# design.net
KiCad netlist of a schematic drawn in Altium Designer
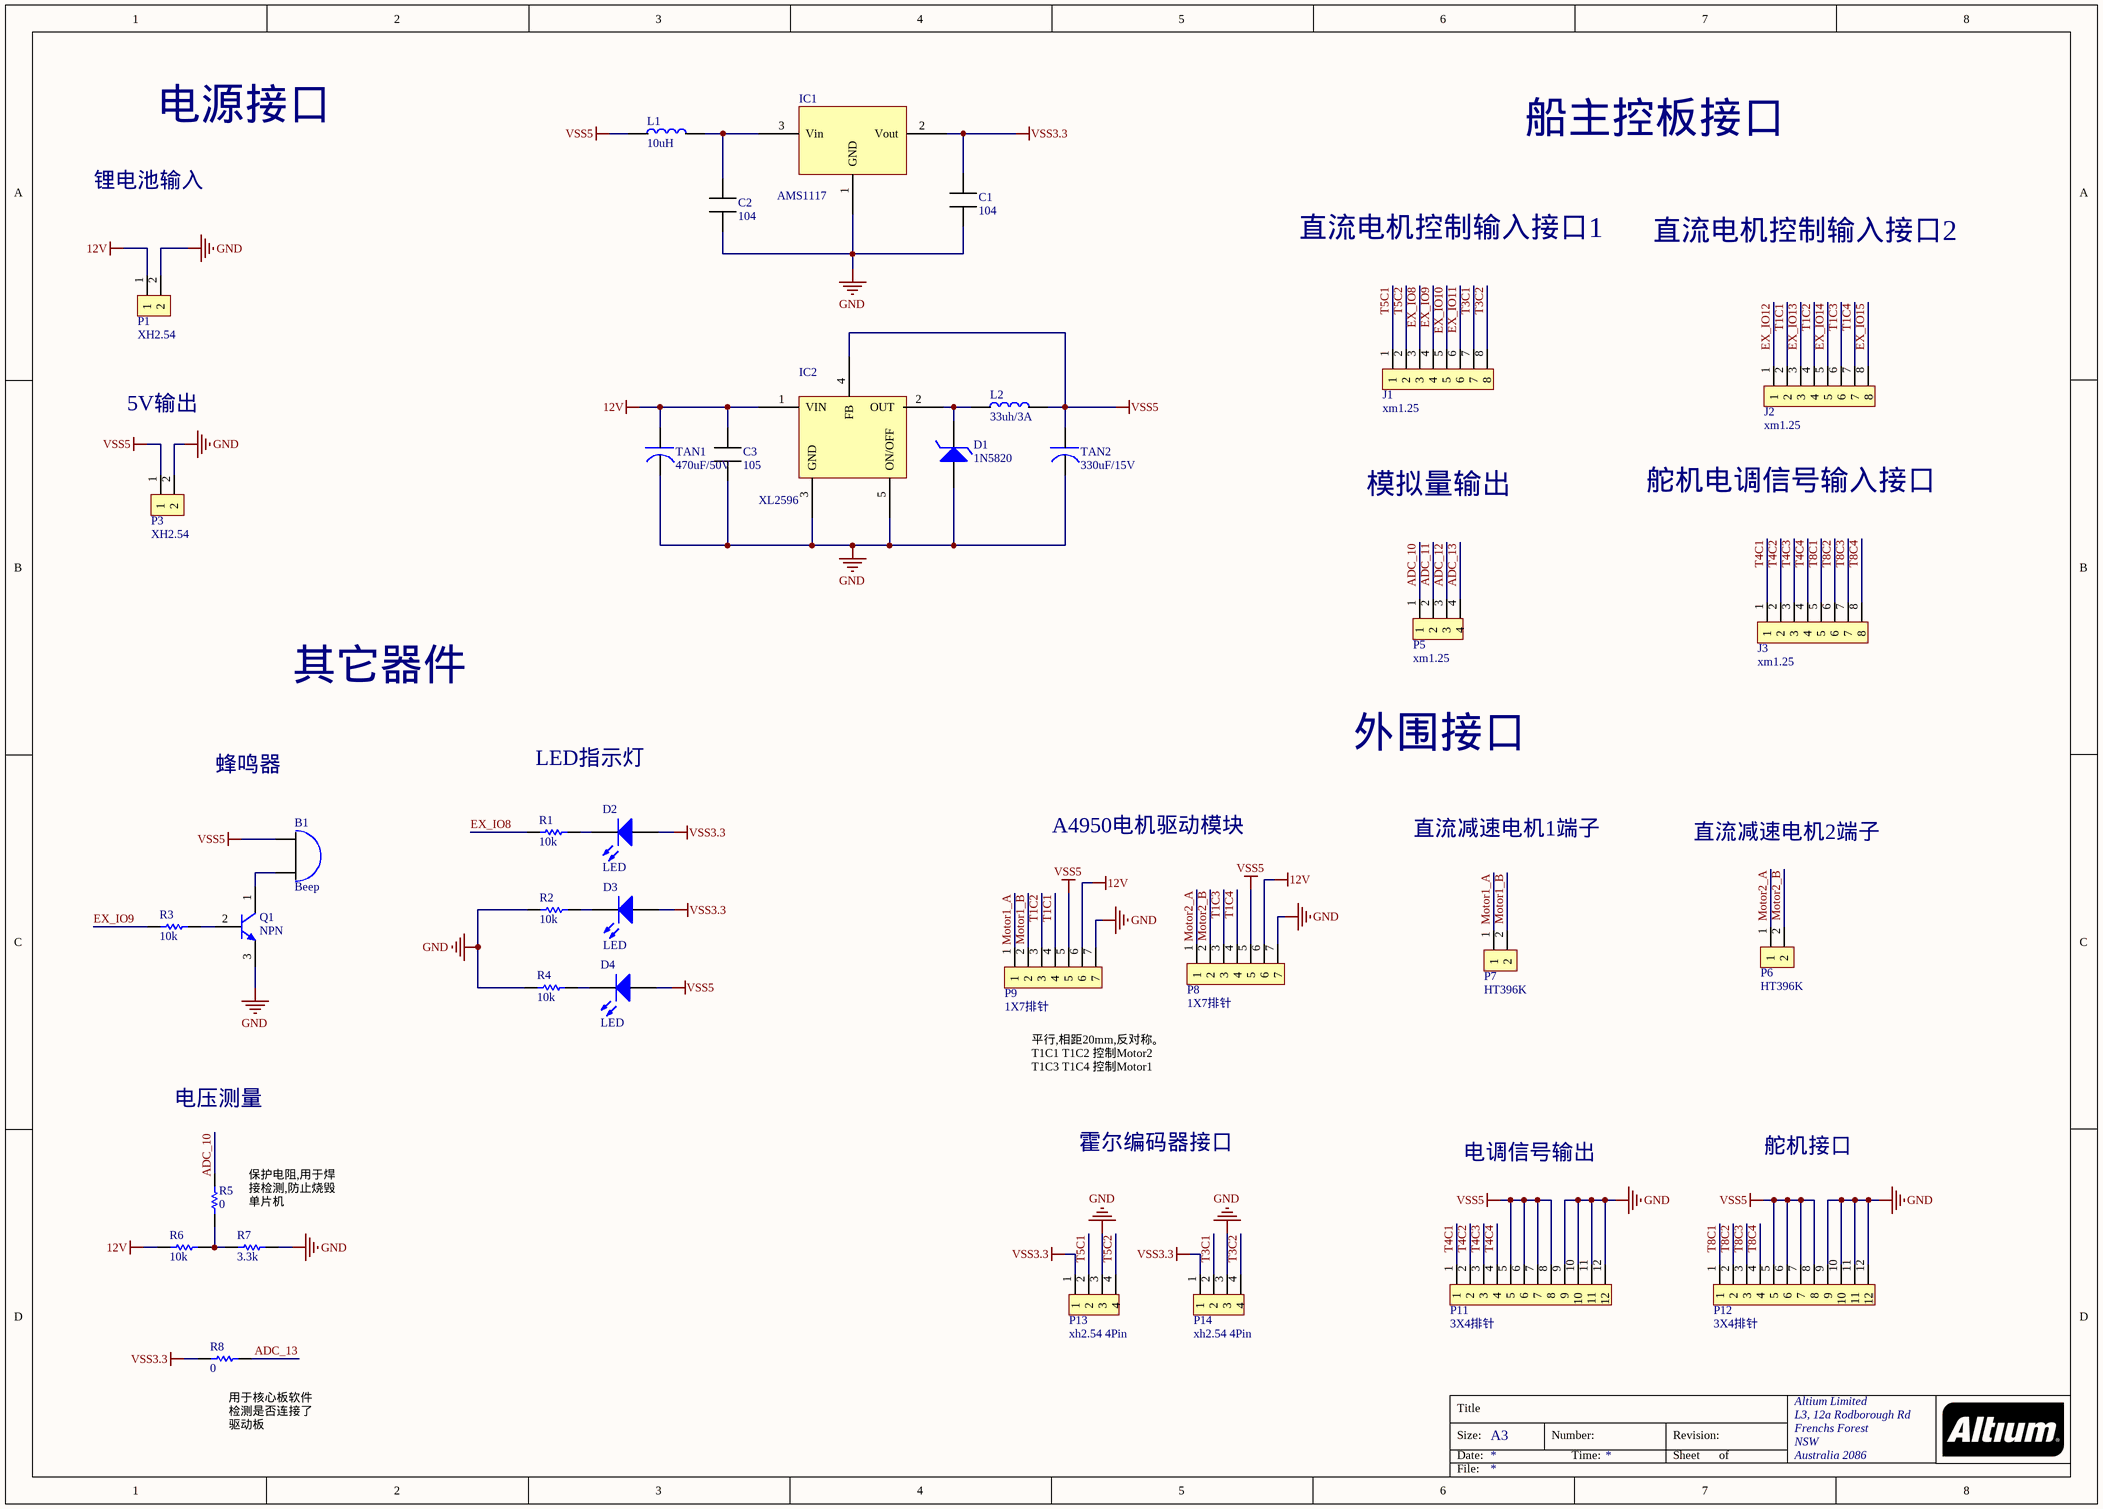
[diagram p0: 船驱动板.SchDoc]

(export (version "E")
  (design (tool "Eeschema 10.0.6"))
  (components
    (comp (ref "B1") (value "Beep") (footprint "蜂鸣器") (libsource (lib "船驱动板") (part "Beep")))
    (comp (ref "C1") (value "104") (footprint "C 0603") (libsource (lib "船核心板") (part "电容")))
    (comp (ref "C2") (value "104") (footprint "C 0603") (libsource (lib "船核心板") (part "电容")))
    (comp (ref "C3") (value "105") (footprint "C 0603") (libsource (lib "船驱动板") (part "电容")))
    (comp (ref "D1") (value "1N5820") (footprint "1N5824") (libsource (lib "船驱动板") (part "稳压二极管")))
    (comp (ref "D2")
      (value "LED")
      (footprint "LED 0603")
      (description "Typical INFRARED GaAs LED")
      (fields (field (name "PUBLISHER") "Altium Limited"))
      (libsource (lib "船核心板") (part "LED"))
    )
    (comp (ref "D3")
      (value "LED")
      (footprint "LED 0603")
      (description "Typical INFRARED GaAs LED")
      (fields (field (name "PUBLISHER") "Altium Limited"))
      (libsource (lib "船核心板") (part "LED"))
    )
    (comp (ref "D4")
      (value "LED")
      (footprint "LED 0603")
      (description "Typical INFRARED GaAs LED")
      (fields (field (name "PUBLISHER") "Altium Limited"))
      (libsource (lib "船核心板") (part "LED"))
    )
    (comp (ref "IC1") (value "AMS1117") (footprint "SOT-223") (libsource (lib "船核心板") (part "AMS1117-3.3")))
    (comp (ref "IC2") (value "XL2596") (footprint "TO-263-5") (libsource (lib "船驱动板") (part "XL2596")))
    (comp (ref "J1") (value "xm1.25") (footprint "MX1.25 8P LS") (libsource (lib "船核心板") (part "1X8排针")))
    (comp (ref "J2") (value "xm1.25") (footprint "MX1.25 8P LS") (libsource (lib "船核心板") (part "1X8排针")))
    (comp (ref "J3") (value "xm1.25") (footprint "MX1.25 8P LS") (libsource (lib "船核心板") (part "1X8排针")))
    (comp (ref "L1") (value "10uH") (footprint "L 0603") (libsource (lib "船核心板") (part "电感")))
    (comp (ref "L2") (value "33uh/3A") (footprint "CDRH74") (libsource (lib "船核心板") (part "电感")))
    (comp (ref "P1") (value "XH2.54") (footprint "XH2.54 2P") (libsource (lib "船驱动板") (part "1X2排针")))
    (comp (ref "P3") (value "XH2.54") (footprint "XH2.54 2P") (libsource (lib "船驱动板") (part "1X2排针")))
    (comp (ref "P5") (value "xm1.25") (footprint "MX1.25") (libsource (lib "船核心板") (part "1X4排针")))
    (comp (ref "P6") (value "HT396K") (footprint "HT396 - 2P") (libsource (lib "船驱动板") (part "1X2排针")))
    (comp (ref "P7") (value "HT396K") (footprint "HT396 - 2P") (libsource (lib "船驱动板") (part "1X2排针")))
    (comp (ref "P8") (value "1X7排针") (footprint "2.54 1X7Pin") (libsource (lib "船驱动板") (part "1X7排针")))
    (comp (ref "P9") (value "1X7排针") (footprint "2.54 1X7Pin") (libsource (lib "船驱动板") (part "1X7排针")))
    (comp (ref "P11") (value "3X4排针") (footprint "2.54 3X4") (libsource (lib "船驱动板") (part "3X4排针")))
    (comp (ref "P12") (value "3X4排针") (footprint "2.54 3X4") (libsource (lib "船驱动板") (part "3X4排针")))
    (comp (ref "P13") (value "xh2.54 4Pin") (footprint "XH2.54 -4p") (libsource (lib "船驱动板") (part "1X4排针")))
    (comp (ref "P14") (value "xh2.54 4Pin") (footprint "XH2.54 -4p") (libsource (lib "船驱动板") (part "1X4排针")))
    (comp (ref "Q1")
      (value "NPN")
      (footprint "SOT-23")
      (description "NPN Bipolar Transistor")
      (fields (field (name "PUBLISHER") "Altium Limited"))
      (libsource (lib "Miscellaneous Devices") (part "NPN"))
    )
    (comp (ref "R1")
      (value "10k")
      (footprint "R 0603")
      (description "Resistor")
      (fields (field (name "PUBLISHER") "Altium Limited"))
      (libsource (lib "船核心板") (part "Res"))
    )
    (comp (ref "R2")
      (value "10k")
      (footprint "R 0603")
      (description "Resistor")
      (fields (field (name "PUBLISHER") "Altium Limited"))
      (libsource (lib "船核心板") (part "Res"))
    )
    (comp (ref "R3")
      (value "10k")
      (footprint "R 0603")
      (description "Resistor")
      (fields (field (name "PUBLISHER") "Altium Limited"))
      (libsource (lib "船驱动板") (part "Res"))
    )
    (comp (ref "R4")
      (value "10k")
      (footprint "R 0603")
      (description "Resistor")
      (fields (field (name "PUBLISHER") "Altium Limited"))
      (libsource (lib "船核心板") (part "Res"))
    )
    (comp (ref "R5")
      (value "0")
      (footprint "R 0603")
      (description "Resistor")
      (fields (field (name "PUBLISHER") "Altium Limited"))
      (libsource (lib "船驱动板") (part "Res"))
    )
    (comp (ref "R6")
      (value "10k")
      (footprint "R 0603")
      (description "Resistor")
      (fields (field (name "PUBLISHER") "Altium Limited"))
      (libsource (lib "船驱动板") (part "Res"))
    )
    (comp (ref "R7")
      (value "3.3k")
      (footprint "R 0603")
      (description "Resistor")
      (fields (field (name "PUBLISHER") "Altium Limited"))
      (libsource (lib "船驱动板") (part "Res"))
    )
    (comp (ref "R8")
      (value "0")
      (footprint "R 0603")
      (description "Resistor")
      (fields (field (name "PUBLISHER") "Altium Limited"))
      (libsource (lib "船驱动板") (part "Res"))
    )
    (comp (ref "TAN1")
      (value "470uF/50V")
      (footprint "10X10.5mm 电解电容")
      (libsource (lib "船驱动板") (part "极性电容"))
    )
    (comp (ref "TAN2") (value "330uF/15V") (footprint "8*10.0mm 电解电容") (libsource (lib "船驱动板") (part "极性电容")))
  )
  (nets
    (net (code "1") (name "/ADC_10") (class "Default")
      (node (ref "P5") (pin "1") (pinfunction "1_1") (pintype "passive"))
      (node (ref "R5") (pin "2") (pinfunction "2_2") (pintype "passive"))
    )
    (net (code "2") (name "/ADC_11") (class "Default")
      (node (ref "P5") (pin "2") (pinfunction "2_2") (pintype "passive"))
    )
    (net (code "3") (name "/ADC_12") (class "Default")
      (node (ref "P5") (pin "3") (pinfunction "3_3") (pintype "passive"))
    )
    (net (code "4") (name "/ADC_13") (class "Default")
      (node (ref "P5") (pin "4") (pinfunction "4_4") (pintype "passive"))
      (node (ref "R8") (pin "2") (pinfunction "2_2") (pintype "passive"))
    )
    (net (code "5") (name "/EX_IO8") (class "Default")
      (node (ref "J1") (pin "3") (pinfunction "3_3") (pintype "passive"))
      (node (ref "R1") (pin "1") (pinfunction "1_1") (pintype "passive"))
    )
    (net (code "6") (name "/EX_IO9") (class "Default")
      (node (ref "J1") (pin "4") (pinfunction "4_4") (pintype "passive"))
      (node (ref "R3") (pin "1") (pinfunction "1_1") (pintype "passive"))
    )
    (net (code "7") (name "/EX_IO10") (class "Default")
      (node (ref "J1") (pin "5") (pinfunction "5_5") (pintype "passive"))
    )
    (net (code "8") (name "/EX_IO11") (class "Default")
      (node (ref "J1") (pin "6") (pinfunction "6_6") (pintype "passive"))
    )
    (net (code "9") (name "/EX_IO12") (class "Default")
      (node (ref "J2") (pin "1") (pinfunction "1_1") (pintype "passive"))
    )
    (net (code "10") (name "/EX_IO13") (class "Default")
      (node (ref "J2") (pin "3") (pinfunction "3_3") (pintype "passive"))
    )
    (net (code "11") (name "/EX_IO14") (class "Default")
      (node (ref "J2") (pin "5") (pinfunction "5_5") (pintype "passive"))
    )
    (net (code "12") (name "/EX_IO15") (class "Default")
      (node (ref "J2") (pin "8") (pinfunction "8_8") (pintype "passive"))
    )
    (net (code "13") (name "/Motor1_A") (class "Default")
      (node (ref "P7") (pin "1") (pinfunction "1_1") (pintype "passive"))
      (node (ref "P9") (pin "1") (pinfunction "1_1") (pintype "passive"))
    )
    (net (code "14") (name "/Motor1_B") (class "Default")
      (node (ref "P7") (pin "2") (pinfunction "2_2") (pintype "passive"))
      (node (ref "P9") (pin "2") (pinfunction "2_2") (pintype "passive"))
    )
    (net (code "15") (name "/Motor2_A") (class "Default")
      (node (ref "P6") (pin "1") (pinfunction "1_1") (pintype "passive"))
      (node (ref "P8") (pin "1") (pinfunction "1_1") (pintype "passive"))
    )
    (net (code "16") (name "/Motor2_B") (class "Default")
      (node (ref "P6") (pin "2") (pinfunction "2_2") (pintype "passive"))
      (node (ref "P8") (pin "2") (pinfunction "2_2") (pintype "passive"))
    )
    (net (code "17") (name "/T1C1") (class "Default")
      (node (ref "J2") (pin "2") (pinfunction "2_2") (pintype "passive"))
      (node (ref "P9") (pin "4") (pinfunction "4_4") (pintype "passive"))
    )
    (net (code "18") (name "/T1C2") (class "Default")
      (node (ref "J2") (pin "4") (pinfunction "4_4") (pintype "passive"))
      (node (ref "P9") (pin "3") (pinfunction "3_3") (pintype "passive"))
    )
    (net (code "19") (name "/T1C3") (class "Default")
      (node (ref "J2") (pin "6") (pinfunction "6_6") (pintype "passive"))
      (node (ref "P8") (pin "3") (pinfunction "3_3") (pintype "passive"))
    )
    (net (code "20") (name "/T1C4") (class "Default")
      (node (ref "J2") (pin "7") (pinfunction "7_7") (pintype "passive"))
      (node (ref "P8") (pin "4") (pinfunction "4_4") (pintype "passive"))
    )
    (net (code "21") (name "/T3C1") (class "Default")
      (node (ref "J1") (pin "7") (pinfunction "7_7") (pintype "passive"))
      (node (ref "P14") (pin "2") (pinfunction "2_2") (pintype "passive"))
    )
    (net (code "22") (name "/T3C2") (class "Default")
      (node (ref "J1") (pin "8") (pinfunction "8_8") (pintype "passive"))
      (node (ref "P14") (pin "4") (pinfunction "4_4") (pintype "passive"))
    )
    (net (code "23") (name "/T4C1") (class "Default")
      (node (ref "J3") (pin "1") (pinfunction "1_1") (pintype "passive"))
      (node (ref "P11") (pin "1") (pinfunction "1_1") (pintype "passive"))
    )
    (net (code "24") (name "/T4C2") (class "Default")
      (node (ref "J3") (pin "2") (pinfunction "2_2") (pintype "passive"))
      (node (ref "P11") (pin "2") (pinfunction "2_2") (pintype "passive"))
    )
    (net (code "25") (name "/T4C3") (class "Default")
      (node (ref "J3") (pin "3") (pinfunction "3_3") (pintype "passive"))
      (node (ref "P11") (pin "3") (pinfunction "3_3") (pintype "passive"))
    )
    (net (code "26") (name "/T4C4") (class "Default")
      (node (ref "J3") (pin "4") (pinfunction "4_4") (pintype "passive"))
      (node (ref "P11") (pin "4") (pinfunction "4_4") (pintype "passive"))
    )
    (net (code "27") (name "/T5C1") (class "Default")
      (node (ref "J1") (pin "1") (pinfunction "1_1") (pintype "passive"))
      (node (ref "P13") (pin "2") (pinfunction "2_2") (pintype "passive"))
    )
    (net (code "28") (name "/T5C2") (class "Default")
      (node (ref "J1") (pin "2") (pinfunction "2_2") (pintype "passive"))
      (node (ref "P13") (pin "4") (pinfunction "4_4") (pintype "passive"))
    )
    (net (code "29") (name "/T8C1") (class "Default")
      (node (ref "J3") (pin "5") (pinfunction "5_5") (pintype "passive"))
      (node (ref "P12") (pin "1") (pinfunction "1_1") (pintype "passive"))
    )
    (net (code "30") (name "/T8C2") (class "Default")
      (node (ref "J3") (pin "6") (pinfunction "6_6") (pintype "passive"))
      (node (ref "P12") (pin "2") (pinfunction "2_2") (pintype "passive"))
    )
    (net (code "31") (name "/T8C3") (class "Default")
      (node (ref "J3") (pin "7") (pinfunction "7_7") (pintype "passive"))
      (node (ref "P12") (pin "3") (pinfunction "3_3") (pintype "passive"))
    )
    (net (code "32") (name "/T8C4") (class "Default")
      (node (ref "J3") (pin "8") (pinfunction "8_8") (pintype "passive"))
      (node (ref "P12") (pin "4") (pinfunction "4_4") (pintype "passive"))
    )
    (net (code "33") (name "12V") (class "Default")
      (node (ref "C3") (pin "2") (pinfunction "2_2") (pintype "passive"))
      (node (ref "IC2") (pin "1") (pinfunction "VIN_1") (pintype "passive"))
      (node (ref "P1") (pin "1") (pinfunction "1_1") (pintype "passive"))
      (node (ref "P8") (pin "6") (pinfunction "6_6") (pintype "passive"))
      (node (ref "P9") (pin "6") (pinfunction "6_6") (pintype "passive"))
      (node (ref "R6") (pin "1") (pinfunction "1_1") (pintype "passive"))
      (node (ref "TAN1") (pin "2") (pinfunction "2_2") (pintype "passive"))
    )
    (net (code "34") (name "GND") (class "Default")
      (node (ref "C1") (pin "1") (pinfunction "1_1") (pintype "passive"))
      (node (ref "C2") (pin "1") (pinfunction "1_1") (pintype "passive"))
      (node (ref "C3") (pin "1") (pinfunction "1_1") (pintype "passive"))
      (node (ref "D1") (pin "1") (pinfunction "A_1") (pintype "passive"))
      (node (ref "IC1") (pin "1") (pinfunction "GND_1") (pintype "passive"))
      (node (ref "IC2") (pin "3") (pinfunction "GND_3") (pintype "passive"))
      (node (ref "IC2") (pin "5") (pinfunction "ON/OFF_5") (pintype "passive"))
      (node (ref "P1") (pin "2") (pinfunction "2_2") (pintype "passive"))
      (node (ref "P11") (pin "10") (pinfunction "10_10") (pintype "passive"))
      (node (ref "P11") (pin "11") (pinfunction "11_11") (pintype "passive"))
      (node (ref "P11") (pin "12") (pinfunction "12_12") (pintype "passive"))
      (node (ref "P11") (pin "9") (pinfunction "9_9") (pintype "passive"))
      (node (ref "P12") (pin "10") (pinfunction "10_10") (pintype "passive"))
      (node (ref "P12") (pin "11") (pinfunction "11_11") (pintype "passive"))
      (node (ref "P12") (pin "12") (pinfunction "12_12") (pintype "passive"))
      (node (ref "P12") (pin "9") (pinfunction "9_9") (pintype "passive"))
      (node (ref "P13") (pin "3") (pinfunction "3_3") (pintype "passive"))
      (node (ref "P14") (pin "3") (pinfunction "3_3") (pintype "passive"))
      (node (ref "P3") (pin "2") (pinfunction "2_2") (pintype "passive"))
      (node (ref "P8") (pin "7") (pinfunction "7_7") (pintype "passive"))
      (node (ref "P9") (pin "7") (pinfunction "7_7") (pintype "passive"))
      (node (ref "Q1") (pin "3") (pinfunction "E_3") (pintype "passive"))
      (node (ref "R2") (pin "1") (pinfunction "1_1") (pintype "passive"))
      (node (ref "R4") (pin "1") (pinfunction "1_1") (pintype "passive"))
      (node (ref "R7") (pin "2") (pinfunction "2_2") (pintype "passive"))
      (node (ref "TAN1") (pin "1") (pinfunction "1_1") (pintype "passive"))
      (node (ref "TAN2") (pin "1") (pinfunction "1_1") (pintype "passive"))
    )
    (net (code "35") (name "Net-(D1-K)") (class "Default")
      (node (ref "D1") (pin "2") (pinfunction "K_2") (pintype "passive"))
      (node (ref "IC2") (pin "2") (pinfunction "OUT_2") (pintype "passive"))
      (node (ref "L2") (pin "1") (pinfunction "1_1") (pintype "passive"))
    )
    (net (code "36") (name "Net-(D2-K)") (class "Default")
      (node (ref "D2") (pin "2") (pinfunction "K_2") (pintype "passive"))
      (node (ref "R1") (pin "2") (pinfunction "2_2") (pintype "passive"))
    )
    (net (code "37") (name "Net-(D3-K)") (class "Default")
      (node (ref "D3") (pin "2") (pinfunction "K_2") (pintype "passive"))
      (node (ref "R2") (pin "2") (pinfunction "2_2") (pintype "passive"))
    )
    (net (code "38") (name "Net-(D4-K)") (class "Default")
      (node (ref "D4") (pin "2") (pinfunction "K_2") (pintype "passive"))
      (node (ref "R4") (pin "2") (pinfunction "2_2") (pintype "passive"))
    )
    (net (code "39") (name "Net-(IC1-Vin)") (class "Default")
      (node (ref "C2") (pin "2") (pinfunction "2_2") (pintype "passive"))
      (node (ref "IC1") (pin "3") (pinfunction "Vin_3") (pintype "passive"))
      (node (ref "L1") (pin "2") (pinfunction "2_2") (pintype "passive"))
    )
    (net (code "40") (name "Net-(Q1-B)") (class "Default")
      (node (ref "Q1") (pin "2") (pinfunction "B_2") (pintype "passive"))
      (node (ref "R3") (pin "2") (pinfunction "2_2") (pintype "passive"))
    )
    (net (code "41") (name "Net-(Q1-C)") (class "Default")
      (node (ref "B1") (pin "2") (pinfunction "2_2") (pintype "passive"))
      (node (ref "Q1") (pin "1") (pinfunction "C_1") (pintype "passive"))
    )
    (net (code "42") (name "Net-(R5-Pad1)") (class "Default")
      (node (ref "R5") (pin "1") (pinfunction "1_1") (pintype "passive"))
      (node (ref "R6") (pin "2") (pinfunction "2_2") (pintype "passive"))
      (node (ref "R7") (pin "1") (pinfunction "1_1") (pintype "passive"))
    )
    (net (code "43") (name "VSS3.3") (class "Default")
      (node (ref "C1") (pin "2") (pinfunction "2_2") (pintype "passive"))
      (node (ref "D2") (pin "1") (pinfunction "A_1") (pintype "passive"))
      (node (ref "D3") (pin "1") (pinfunction "A_1") (pintype "passive"))
      (node (ref "IC1") (pin "2") (pinfunction "Vout_2") (pintype "passive"))
      (node (ref "P13") (pin "1") (pinfunction "1_1") (pintype "passive"))
      (node (ref "P14") (pin "1") (pinfunction "1_1") (pintype "passive"))
      (node (ref "R8") (pin "1") (pinfunction "1_1") (pintype "passive"))
    )
    (net (code "44") (name "VSS5") (class "Default")
      (node (ref "B1") (pin "1") (pinfunction "1_1") (pintype "passive"))
      (node (ref "D4") (pin "1") (pinfunction "A_1") (pintype "passive"))
      (node (ref "IC2") (pin "4") (pinfunction "FB_4") (pintype "passive"))
      (node (ref "L1") (pin "1") (pinfunction "1_1") (pintype "passive"))
      (node (ref "L2") (pin "2") (pinfunction "2_2") (pintype "passive"))
      (node (ref "P11") (pin "5") (pinfunction "5_5") (pintype "passive"))
      (node (ref "P11") (pin "6") (pinfunction "6_6") (pintype "passive"))
      (node (ref "P11") (pin "7") (pinfunction "7_7") (pintype "passive"))
      (node (ref "P11") (pin "8") (pinfunction "8_8") (pintype "passive"))
      (node (ref "P12") (pin "5") (pinfunction "5_5") (pintype "passive"))
      (node (ref "P12") (pin "6") (pinfunction "6_6") (pintype "passive"))
      (node (ref "P12") (pin "7") (pinfunction "7_7") (pintype "passive"))
      (node (ref "P12") (pin "8") (pinfunction "8_8") (pintype "passive"))
      (node (ref "P3") (pin "1") (pinfunction "1_1") (pintype "passive"))
      (node (ref "P8") (pin "5") (pinfunction "5_5") (pintype "passive"))
      (node (ref "P9") (pin "5") (pinfunction "5_5") (pintype "passive"))
      (node (ref "TAN2") (pin "2") (pinfunction "2_2") (pintype "passive"))
    )
  )
)
